# TSAL_Light_2018-2019_v1.net
KiCad netlist of a schematic drawn in Altium Designer
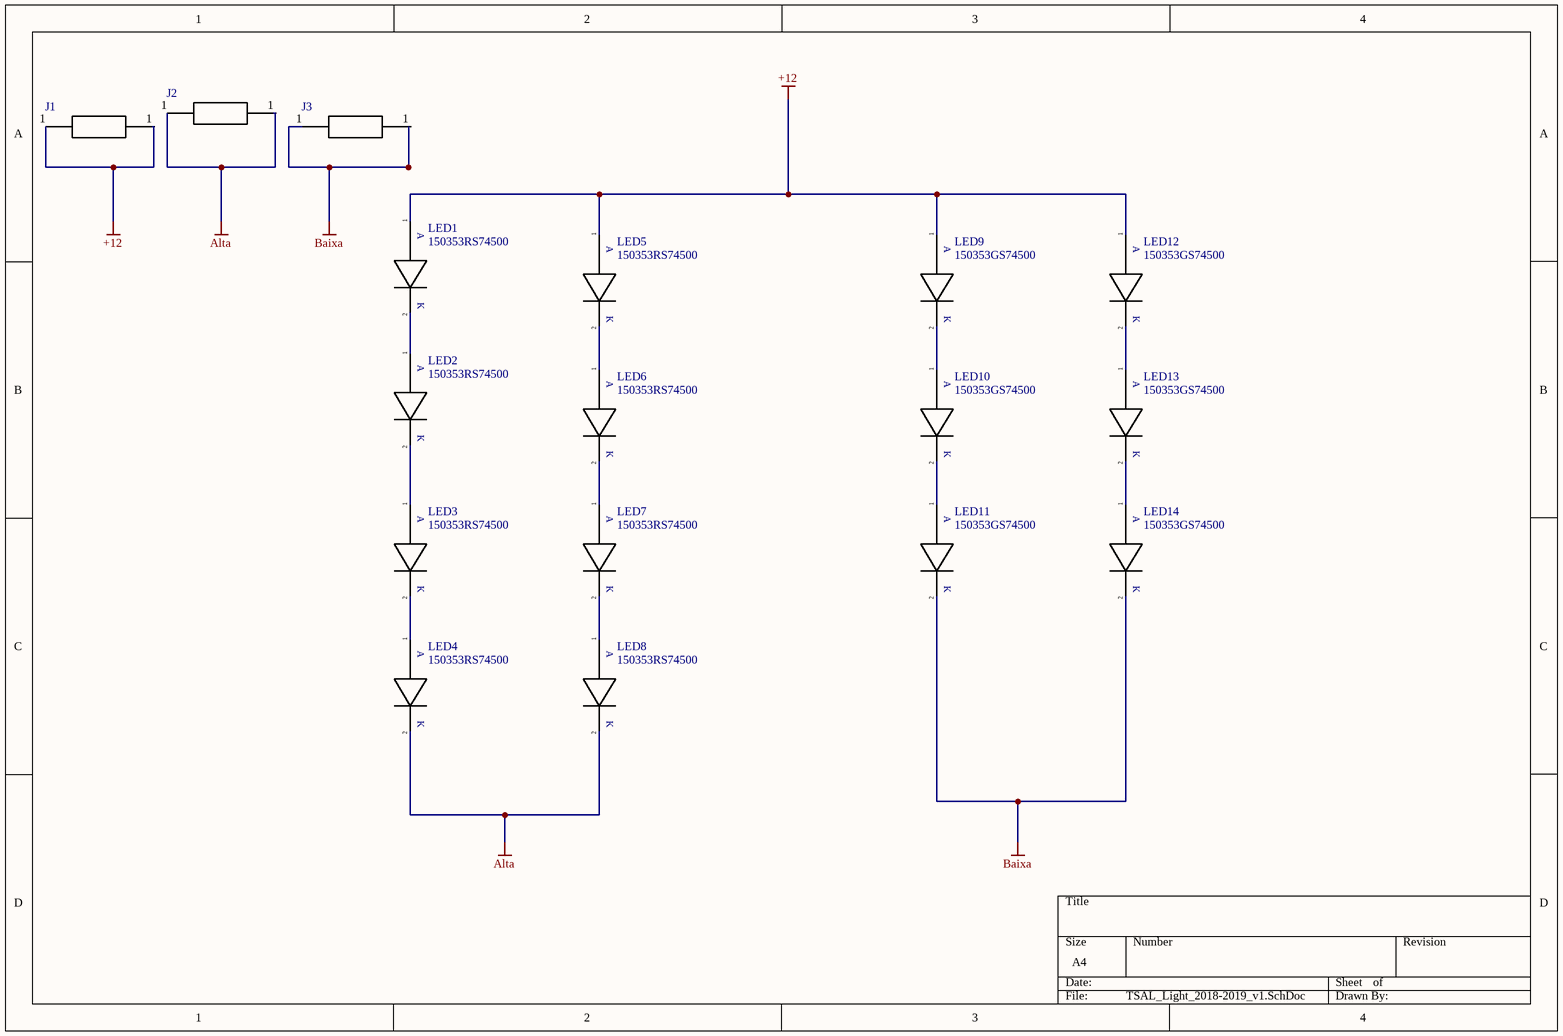
[diagram p0: TSAL_Light_2018-2019_v1.SchDoc]

(export (version "E")
  (design (tool "Eeschema 10.0.6"))
  (components
    (comp (ref "J1") (value "Pad") (footprint "Pad") (libsource (lib "pad") (part "Pad")))
    (comp (ref "J2") (value "Pad") (footprint "Pad") (libsource (lib "pad") (part "Pad")))
    (comp (ref "J3") (value "Pad") (footprint "Pad") (libsource (lib "pad") (part "Pad")))
    (comp (ref "LED1")
      (value "150353RS74500")
      (footprint "150353RS74500")
      (libsource (lib "150353RS74500") (part "150353RS74500"))
    )
    (comp (ref "LED2")
      (value "150353RS74500")
      (footprint "150353RS74500")
      (libsource (lib "105353RS74500") (part "150353RS74500"))
    )
    (comp (ref "LED3")
      (value "150353RS74500")
      (footprint "150353RS74500")
      (libsource (lib "105353RS74500") (part "150353RS74500"))
    )
    (comp (ref "LED4")
      (value "150353RS74500")
      (footprint "150353RS74500")
      (libsource (lib "105353RS74500") (part "150353RS74500"))
    )
    (comp (ref "LED5")
      (value "150353RS74500")
      (footprint "150353RS74500")
      (libsource (lib "105353RS74500") (part "150353RS74500"))
    )
    (comp (ref "LED6")
      (value "150353RS74500")
      (footprint "150353RS74500")
      (libsource (lib "105353RS74500") (part "150353RS74500"))
    )
    (comp (ref "LED7")
      (value "150353RS74500")
      (footprint "150353RS74500")
      (libsource (lib "105353RS74500") (part "150353RS74500"))
    )
    (comp (ref "LED8")
      (value "150353RS74500")
      (footprint "150353RS74500")
      (libsource (lib "105353RS74500") (part "150353RS74500"))
    )
    (comp (ref "LED9")
      (value "150353GS74500")
      (footprint "150353RS74500")
      (libsource (lib "105353RS74500") (part "150353RS74500"))
    )
    (comp (ref "LED10")
      (value "150353GS74500")
      (footprint "150353RS74500")
      (libsource (lib "105353RS74500") (part "150353RS74500"))
    )
    (comp (ref "LED11")
      (value "150353GS74500")
      (footprint "150353RS74500")
      (libsource (lib "105353RS74500") (part "150353RS74500"))
    )
    (comp (ref "LED12")
      (value "150353GS74500")
      (footprint "150353RS74500")
      (libsource (lib "105353RS74500") (part "150353RS74500"))
    )
    (comp (ref "LED13")
      (value "150353GS74500")
      (footprint "150353RS74500")
      (libsource (lib "105353RS74500") (part "150353RS74500"))
    )
    (comp (ref "LED14")
      (value "150353GS74500")
      (footprint "150353RS74500")
      (libsource (lib "105353RS74500") (part "150353RS74500"))
    )
  )
  (nets
    (net (code "1") (name "+12") (class "Default")
      (node (ref "J1") (pin "1") (pinfunction "1_1") (pintype "passive"))
      (node (ref "LED1") (pin "1") (pinfunction "1_1") (pintype "passive"))
      (node (ref "LED12") (pin "1") (pinfunction "1_1") (pintype "passive"))
      (node (ref "LED5") (pin "1") (pinfunction "1_1") (pintype "passive"))
      (node (ref "LED9") (pin "1") (pinfunction "1_1") (pintype "passive"))
    )
    (net (code "2") (name "Alta") (class "Default")
      (node (ref "J2") (pin "1") (pinfunction "1_1") (pintype "passive"))
      (node (ref "LED4") (pin "2") (pinfunction "2_2") (pintype "passive"))
      (node (ref "LED8") (pin "2") (pinfunction "2_2") (pintype "passive"))
    )
    (net (code "3") (name "Baixa") (class "Default")
      (node (ref "J3") (pin "1") (pinfunction "1_1") (pintype "passive"))
      (node (ref "LED11") (pin "2") (pinfunction "2_2") (pintype "passive"))
      (node (ref "LED14") (pin "2") (pinfunction "2_2") (pintype "passive"))
    )
    (net (code "4") (name "Net-(LED1-Pad2)") (class "Default")
      (node (ref "LED1") (pin "2") (pinfunction "2_2") (pintype "passive"))
      (node (ref "LED2") (pin "1") (pinfunction "1_1") (pintype "passive"))
    )
    (net (code "5") (name "Net-(LED2-Pad2)") (class "Default")
      (node (ref "LED2") (pin "2") (pinfunction "2_2") (pintype "passive"))
      (node (ref "LED3") (pin "1") (pinfunction "1_1") (pintype "passive"))
    )
    (net (code "6") (name "Net-(LED3-Pad2)") (class "Default")
      (node (ref "LED3") (pin "2") (pinfunction "2_2") (pintype "passive"))
      (node (ref "LED4") (pin "1") (pinfunction "1_1") (pintype "passive"))
    )
    (net (code "7") (name "Net-(LED5-Pad2)") (class "Default")
      (node (ref "LED5") (pin "2") (pinfunction "2_2") (pintype "passive"))
      (node (ref "LED6") (pin "1") (pinfunction "1_1") (pintype "passive"))
    )
    (net (code "8") (name "Net-(LED6-Pad2)") (class "Default")
      (node (ref "LED6") (pin "2") (pinfunction "2_2") (pintype "passive"))
      (node (ref "LED7") (pin "1") (pinfunction "1_1") (pintype "passive"))
    )
    (net (code "9") (name "Net-(LED7-Pad2)") (class "Default")
      (node (ref "LED7") (pin "2") (pinfunction "2_2") (pintype "passive"))
      (node (ref "LED8") (pin "1") (pinfunction "1_1") (pintype "passive"))
    )
    (net (code "10") (name "Net-(LED10-Pad1)") (class "Default")
      (node (ref "LED10") (pin "1") (pinfunction "1_1") (pintype "passive"))
      (node (ref "LED9") (pin "2") (pinfunction "2_2") (pintype "passive"))
    )
    (net (code "11") (name "Net-(LED10-Pad2)") (class "Default")
      (node (ref "LED10") (pin "2") (pinfunction "2_2") (pintype "passive"))
      (node (ref "LED11") (pin "1") (pinfunction "1_1") (pintype "passive"))
    )
    (net (code "12") (name "Net-(LED12-Pad2)") (class "Default")
      (node (ref "LED12") (pin "2") (pinfunction "2_2") (pintype "passive"))
      (node (ref "LED13") (pin "1") (pinfunction "1_1") (pintype "passive"))
    )
    (net (code "13") (name "Net-(LED13-Pad2)") (class "Default")
      (node (ref "LED13") (pin "2") (pinfunction "2_2") (pintype "passive"))
      (node (ref "LED14") (pin "1") (pinfunction "1_1") (pintype "passive"))
    )
  )
)
